# arduboy-gt.net
KiCad netlist of a schematic drawn in EAGLE
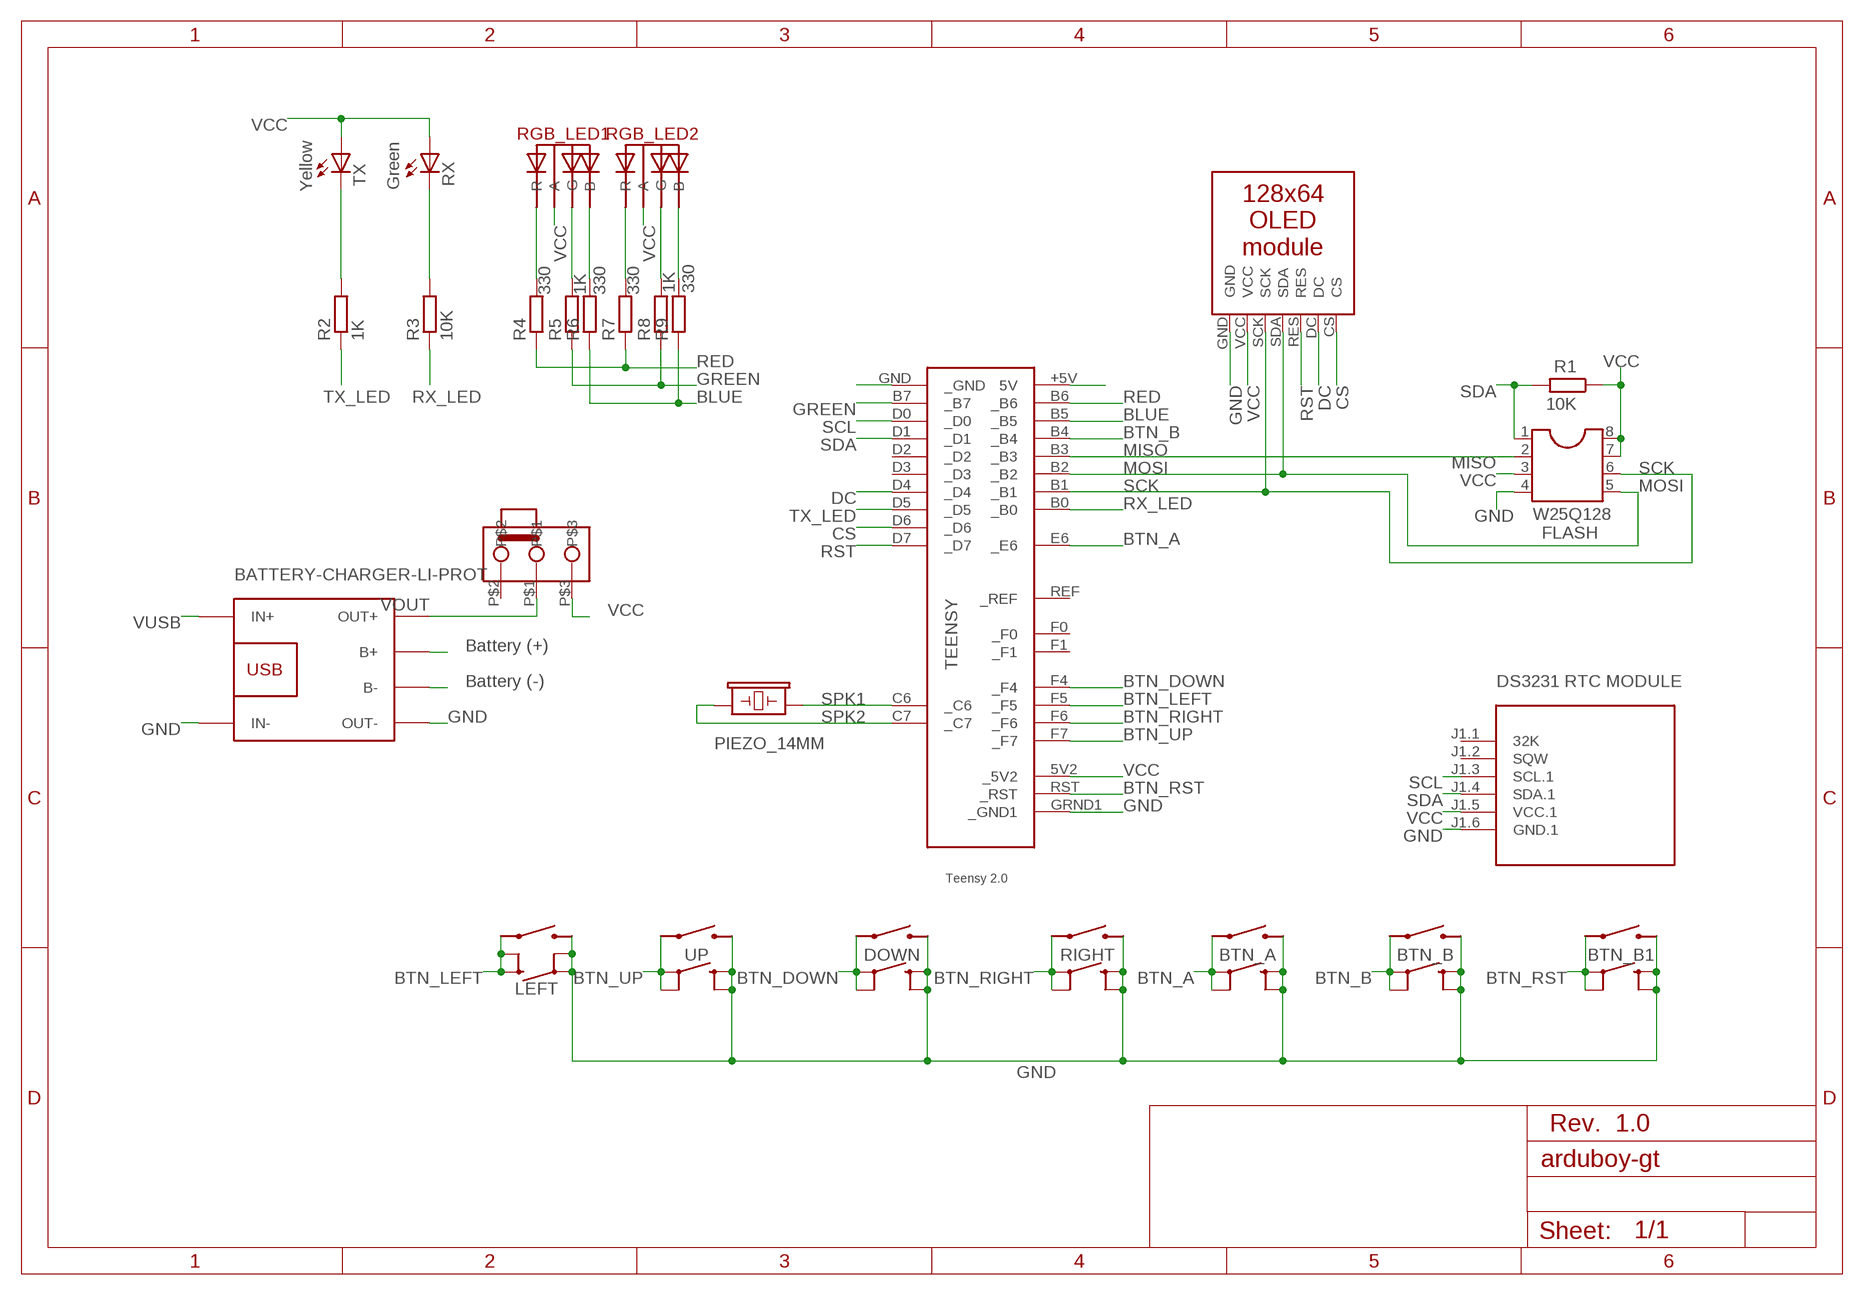
[diagram p0: schematic, sheet 1]

(export (version "E")
  (design (tool "Eeschema 10.0.6"))
  (components
    (comp (ref "BTN_A")
      (value "MOMENTARY-SWITCH-SPST-PTH-6.0MM")
      (footprint "eagle-import:TACTILE_SWITCH_PTH_6.0MM")
      (libsource (lib "eagle-import") (part "MOMENTARY-SWITCH-SPST-PTH-6.0MM"))
    )
    (comp (ref "BTN_A_")
      (value "KAIHLMICROSWITCH")
      (footprint "eagle-import:KAIHLMICROSWITCH")
      (libsource (lib "eagle-import") (part "KAIHLMICROSWITCH"))
    )
    (comp (ref "BTN_B")
      (value "MOMENTARY-SWITCH-SPST-PTH-6.0MM")
      (footprint "eagle-import:TACTILE_SWITCH_PTH_6.0MM")
      (libsource (lib "eagle-import") (part "MOMENTARY-SWITCH-SPST-PTH-6.0MM"))
    )
    (comp (ref "BTN_B1")
      (value "MOMENTARY-SWITCH-SPST-PTH-6.0MM")
      (footprint "eagle-import:TACTILE_SWITCH_PTH_6.0MM")
      (libsource (lib "eagle-import") (part "MOMENTARY-SWITCH-SPST-PTH-6.0MM"))
    )
    (comp (ref "BTN_B_")
      (value "KAIHLMICROSWITCH")
      (footprint "eagle-import:KAIHLMICROSWITCH")
      (libsource (lib "eagle-import") (part "KAIHLMICROSWITCH"))
    )
    (comp (ref "BTN_B_1")
      (value "KAIHLMICROSWITCH")
      (footprint "eagle-import:KAIHLMICROSWITCH")
      (libsource (lib "eagle-import") (part "KAIHLMICROSWITCH"))
    )
    (comp (ref "DOWN")
      (value "MOMENTARY-SWITCH-SPST-PTH-6.0MM")
      (footprint "eagle-import:TACTILE_SWITCH_PTH_6.0MM")
      (libsource (lib "eagle-import") (part "MOMENTARY-SWITCH-SPST-PTH-6.0MM"))
    )
    (comp (ref "DOWN_")
      (value "KAIHLMICROSWITCH")
      (footprint "eagle-import:KAIHLMICROSWITCH")
      (libsource (lib "eagle-import") (part "KAIHLMICROSWITCH"))
    )
    (comp (ref "FLASH")
      (value "W25Q128")
      (footprint "eagle-import:DIL08")
      (libsource (lib "eagle-import") (part "DIL8"))
    )
    (comp (ref "LEFT")
      (value "MOMENTARY-SWITCH-SPST-PTH-6.0MM")
      (footprint "eagle-import:TACTILE_SWITCH_PTH_6.0MM")
      (libsource (lib "eagle-import") (part "MOMENTARY-SWITCH-SPST-PTH-6.0MM"))
    )
    (comp (ref "LEFT_")
      (value "KAIHLMICROSWITCH")
      (footprint "eagle-import:KAIHLMICROSWITCH")
      (libsource (lib "eagle-import") (part "KAIHLMICROSWITCH"))
    )
    (comp (ref "R1")
      (value "10K")
      (footprint "eagle-import:0204_7")
      (libsource (lib "eagle-import") (part "R-EU_0204/7"))
    )
    (comp (ref "R2")
      (value "1K")
      (footprint "eagle-import:0204_7")
      (libsource (lib "eagle-import") (part "R-EU_0204/7"))
    )
    (comp (ref "R3")
      (value "10K")
      (footprint "eagle-import:0204_7")
      (libsource (lib "eagle-import") (part "R-EU_0204/7"))
    )
    (comp (ref "R4")
      (value "330")
      (footprint "eagle-import:0204_7")
      (libsource (lib "eagle-import") (part "R-EU_0204/7"))
    )
    (comp (ref "R5")
      (value "1K")
      (footprint "eagle-import:0204_7")
      (libsource (lib "eagle-import") (part "R-EU_0204/7"))
    )
    (comp (ref "R6")
      (value "330")
      (footprint "eagle-import:0204_7")
      (libsource (lib "eagle-import") (part "R-EU_0204/7"))
    )
    (comp (ref "R7")
      (value "330")
      (footprint "eagle-import:0204_7")
      (libsource (lib "eagle-import") (part "R-EU_0204/7"))
    )
    (comp (ref "R8")
      (value "1K")
      (footprint "eagle-import:0204_7")
      (libsource (lib "eagle-import") (part "R-EU_0204/7"))
    )
    (comp (ref "R9")
      (value "330")
      (footprint "eagle-import:0204_7")
      (libsource (lib "eagle-import") (part "R-EU_0204/7"))
    )
    (comp (ref "RGB_LED1")
      (value "5MMRGBLED-CA")
      (footprint "eagle-import:LED5MMRGB")
      (libsource (lib "eagle-import") (part "5MMRGBLED-CA"))
    )
    (comp (ref "RGB_LED2")
      (value "5MMRGBLED-CA")
      (footprint "eagle-import:LED5MMRGB")
      (libsource (lib "eagle-import") (part "5MMRGBLED-CA"))
    )
    (comp (ref "RIGHT")
      (value "MOMENTARY-SWITCH-SPST-PTH-6.0MM")
      (footprint "eagle-import:TACTILE_SWITCH_PTH_6.0MM")
      (libsource (lib "eagle-import") (part "MOMENTARY-SWITCH-SPST-PTH-6.0MM"))
    )
    (comp (ref "RIGHT_")
      (value "KAIHLMICROSWITCH")
      (footprint "eagle-import:KAIHLMICROSWITCH")
      (libsource (lib "eagle-import") (part "KAIHLMICROSWITCH"))
    )
    (comp (ref "RX")
      (value "TLLG4400")
      (footprint "eagle-import:LED3MM")
      (fields (field (name "MF") "VISHAY SEMICONDUCTOR"))
      (libsource (lib "eagle-import") (part "TLLG4400"))
    )
    (comp (ref "SG1")
      (value "PIEZO_14MM")
      (footprint "eagle-import:PIEZO_14MM")
      (libsource (lib "eagle-import") (part "PIEZO_14MM"))
    )
    (comp (ref "TX")
      (value "TLLY4400")
      (footprint "eagle-import:LED3MM")
      (fields (field (name "MF") "VISHAY SEMICONDUCTOR"))
      (libsource (lib "eagle-import") (part "TLLY4400"))
    )
    (comp (ref "U$1")
      (value "OLED")
      (footprint "eagle-import:OLED")
      (libsource (lib "eagle-import") (part "OLED"))
    )
    (comp (ref "U$2")
      (value "SWITCH")
      (footprint "eagle-import:SWITCH")
      (libsource (lib "eagle-import") (part "SWITCH"))
    )
    (comp (ref "U$3")
      (value "BATTERY-CHARGER-LI-PROT")
      (footprint "eagle-import:BATTERY-CHARGER-LI-PROT")
      (libsource (lib "eagle-import") (part "BATTERY-CHARGER-LI-PROT"))
    )
    (comp (ref "U$6")
      (value "DS3231 RTC MODULE")
      (footprint "eagle-import:RTC-DS3231-AT24C32")
      (libsource (lib "eagle-import") (part "RTC-DS3231-AT24C32"))
    )
    (comp (ref "UP")
      (value "MOMENTARY-SWITCH-SPST-PTH-6.0MM")
      (footprint "eagle-import:TACTILE_SWITCH_PTH_6.0MM")
      (libsource (lib "eagle-import") (part "MOMENTARY-SWITCH-SPST-PTH-6.0MM"))
    )
    (comp (ref "UP_")
      (value "KAIHLMICROSWITCH")
      (footprint "eagle-import:KAIHLMICROSWITCH")
      (libsource (lib "eagle-import") (part "KAIHLMICROSWITCH"))
    )
    (comp (ref "_1")
      (value "TEENSY")
      (footprint "eagle-import:TEENSY")
      (libsource (lib "eagle-import") (part "TEENSY"))
    )
  )
  (nets
    (net (code "1") (name "/BLUE") (class "Default")
      (node (ref "R6") (pin "1") (pinfunction "1_1") (pintype "passive"))
      (node (ref "R9") (pin "1") (pinfunction "1_1") (pintype "passive"))
      (node (ref "_1") (pin "B5") (pinfunction "_B5_B5") (pintype "bidirectional"))
    )
    (net (code "2") (name "/BTN_A") (class "Default")
      (node (ref "BTN_A") (pin "1") (pinfunction "1_1") (pintype "passive"))
      (node (ref "BTN_A") (pin "2") (pinfunction "2_2") (pintype "passive"))
      (node (ref "BTN_A_") (pin "P$1") (pinfunction "P$1_P$1") (pintype "bidirectional"))
      (node (ref "_1") (pin "E6") (pinfunction "_E6_E6") (pintype "bidirectional"))
    )
    (net (code "3") (name "/BTN_B") (class "Default")
      (node (ref "BTN_B") (pin "1") (pinfunction "1_1") (pintype "passive"))
      (node (ref "BTN_B") (pin "2") (pinfunction "2_2") (pintype "passive"))
      (node (ref "BTN_B_") (pin "P$1") (pinfunction "P$1_P$1") (pintype "bidirectional"))
      (node (ref "_1") (pin "B4") (pinfunction "_B4_B4") (pintype "bidirectional"))
    )
    (net (code "4") (name "/BTN_DOWN") (class "Default")
      (node (ref "DOWN") (pin "1") (pinfunction "1_1") (pintype "passive"))
      (node (ref "DOWN") (pin "2") (pinfunction "2_2") (pintype "passive"))
      (node (ref "DOWN_") (pin "P$1") (pinfunction "P$1_P$1") (pintype "bidirectional"))
      (node (ref "_1") (pin "F4") (pinfunction "_F4_F4") (pintype "bidirectional"))
    )
    (net (code "5") (name "/BTN_LEFT") (class "Default")
      (node (ref "LEFT") (pin "3") (pinfunction "3_3") (pintype "passive"))
      (node (ref "LEFT") (pin "4") (pinfunction "4_4") (pintype "passive"))
      (node (ref "LEFT_") (pin "P$1") (pinfunction "P$1_P$1") (pintype "bidirectional"))
      (node (ref "_1") (pin "F5") (pinfunction "_F5_F5") (pintype "bidirectional"))
    )
    (net (code "6") (name "/BTN_RIGHT") (class "Default")
      (node (ref "RIGHT") (pin "1") (pinfunction "1_1") (pintype "passive"))
      (node (ref "RIGHT") (pin "2") (pinfunction "2_2") (pintype "passive"))
      (node (ref "RIGHT_") (pin "P$1") (pinfunction "P$1_P$1") (pintype "bidirectional"))
      (node (ref "_1") (pin "F6") (pinfunction "_F6_F6") (pintype "bidirectional"))
    )
    (net (code "7") (name "/BTN_RST") (class "Default")
      (node (ref "BTN_B1") (pin "1") (pinfunction "1_1") (pintype "passive"))
      (node (ref "BTN_B1") (pin "2") (pinfunction "2_2") (pintype "passive"))
      (node (ref "BTN_B_1") (pin "P$1") (pinfunction "P$1_P$1") (pintype "bidirectional"))
      (node (ref "_1") (pin "RST") (pinfunction "_RST_RST") (pintype "bidirectional"))
    )
    (net (code "8") (name "/BTN_UP") (class "Default")
      (node (ref "UP") (pin "1") (pinfunction "1_1") (pintype "passive"))
      (node (ref "UP") (pin "2") (pinfunction "2_2") (pintype "passive"))
      (node (ref "UP_") (pin "P$1") (pinfunction "P$1_P$1") (pintype "bidirectional"))
      (node (ref "_1") (pin "F7") (pinfunction "_F7_F7") (pintype "bidirectional"))
    )
    (net (code "9") (name "/CS") (class "Default")
      (node (ref "U$1") (pin "CS") (pinfunction "CS_CS") (pintype "input"))
      (node (ref "_1") (pin "D6") (pinfunction "_D6_D6") (pintype "bidirectional"))
    )
    (net (code "10") (name "/DC") (class "Default")
      (node (ref "U$1") (pin "DC") (pinfunction "DC_DC") (pintype "input"))
      (node (ref "_1") (pin "D4") (pinfunction "_D4_D4") (pintype "bidirectional"))
    )
    (net (code "11") (name "/GND") (class "Default")
      (node (ref "BTN_A") (pin "3") (pinfunction "3_3") (pintype "passive"))
      (node (ref "BTN_A") (pin "4") (pinfunction "4_4") (pintype "passive"))
      (node (ref "BTN_A_") (pin "P$2") (pinfunction "P$2_P$2") (pintype "bidirectional"))
      (node (ref "BTN_B") (pin "3") (pinfunction "3_3") (pintype "passive"))
      (node (ref "BTN_B") (pin "4") (pinfunction "4_4") (pintype "passive"))
      (node (ref "BTN_B1") (pin "3") (pinfunction "3_3") (pintype "passive"))
      (node (ref "BTN_B1") (pin "4") (pinfunction "4_4") (pintype "passive"))
      (node (ref "BTN_B_") (pin "P$2") (pinfunction "P$2_P$2") (pintype "bidirectional"))
      (node (ref "BTN_B_1") (pin "P$2") (pinfunction "P$2_P$2") (pintype "bidirectional"))
      (node (ref "DOWN") (pin "3") (pinfunction "3_3") (pintype "passive"))
      (node (ref "DOWN") (pin "4") (pinfunction "4_4") (pintype "passive"))
      (node (ref "DOWN_") (pin "P$2") (pinfunction "P$2_P$2") (pintype "bidirectional"))
      (node (ref "FLASH") (pin "4") (pinfunction "4_4") (pintype "passive"))
      (node (ref "LEFT") (pin "1") (pinfunction "1_1") (pintype "passive"))
      (node (ref "LEFT") (pin "2") (pinfunction "2_2") (pintype "passive"))
      (node (ref "LEFT_") (pin "P$2") (pinfunction "P$2_P$2") (pintype "bidirectional"))
      (node (ref "RIGHT") (pin "3") (pinfunction "3_3") (pintype "passive"))
      (node (ref "RIGHT") (pin "4") (pinfunction "4_4") (pintype "passive"))
      (node (ref "RIGHT_") (pin "P$2") (pinfunction "P$2_P$2") (pintype "bidirectional"))
      (node (ref "U$1") (pin "GND") (pinfunction "GND_GND") (pintype "power_in"))
      (node (ref "U$3") (pin "IN-") (pinfunction "IN-_IN-") (pintype "bidirectional"))
      (node (ref "U$3") (pin "OUT-") (pinfunction "OUT-_OUT-") (pintype "bidirectional"))
      (node (ref "U$6") (pin "J1.6") (pinfunction "GND.1_J1.6") (pintype "power_in"))
      (node (ref "UP") (pin "3") (pinfunction "3_3") (pintype "passive"))
      (node (ref "UP") (pin "4") (pinfunction "4_4") (pintype "passive"))
      (node (ref "UP_") (pin "P$2") (pinfunction "P$2_P$2") (pintype "bidirectional"))
      (node (ref "_1") (pin "GND") (pinfunction "_GND_GND") (pintype "bidirectional"))
      (node (ref "_1") (pin "GRND1") (pinfunction "_GND1_GRND1") (pintype "bidirectional"))
    )
    (net (code "12") (name "/GREEN") (class "Default")
      (node (ref "R5") (pin "1") (pinfunction "1_1") (pintype "passive"))
      (node (ref "R8") (pin "1") (pinfunction "1_1") (pintype "passive"))
      (node (ref "_1") (pin "B7") (pinfunction "_B7_B7") (pintype "bidirectional"))
    )
    (net (code "13") (name "/MISO") (class "Default")
      (node (ref "FLASH") (pin "2") (pinfunction "2_2") (pintype "passive"))
      (node (ref "_1") (pin "B3") (pinfunction "_B3_B3") (pintype "bidirectional"))
    )
    (net (code "14") (name "/MOSI") (class "Default")
      (node (ref "FLASH") (pin "5") (pinfunction "5_5") (pintype "passive"))
      (node (ref "U$1") (pin "SDA") (pinfunction "SDA_SDA") (pintype "input"))
      (node (ref "_1") (pin "B2") (pinfunction "_B2_B2") (pintype "bidirectional"))
    )
    (net (code "15") (name "/RED") (class "Default")
      (node (ref "R4") (pin "1") (pinfunction "1_1") (pintype "passive"))
      (node (ref "R7") (pin "1") (pinfunction "1_1") (pintype "passive"))
      (node (ref "_1") (pin "B6") (pinfunction "_B6_B6") (pintype "bidirectional"))
    )
    (net (code "16") (name "/RST") (class "Default")
      (node (ref "U$1") (pin "RES") (pinfunction "RES_RES") (pintype "input"))
      (node (ref "_1") (pin "D7") (pinfunction "_D7_D7") (pintype "bidirectional"))
    )
    (net (code "17") (name "/RX_LED") (class "Default")
      (node (ref "R3") (pin "1") (pinfunction "1_1") (pintype "passive"))
      (node (ref "_1") (pin "B0") (pinfunction "_B0_B0") (pintype "bidirectional"))
    )
    (net (code "18") (name "/SCK") (class "Default")
      (node (ref "FLASH") (pin "6") (pinfunction "6_6") (pintype "passive"))
      (node (ref "U$1") (pin "SCK") (pinfunction "SCK_SCK") (pintype "input"))
      (node (ref "_1") (pin "B1") (pinfunction "_B1_B1") (pintype "bidirectional"))
    )
    (net (code "19") (name "/SCL") (class "Default")
      (node (ref "U$6") (pin "J1.3") (pinfunction "SCL.1_J1.3") (pintype "bidirectional"))
      (node (ref "_1") (pin "D0") (pinfunction "_D0_D0") (pintype "bidirectional"))
    )
    (net (code "20") (name "/SDA") (class "Default")
      (node (ref "FLASH") (pin "1") (pinfunction "1_1") (pintype "passive"))
      (node (ref "R1") (pin "2") (pinfunction "2_2") (pintype "passive"))
      (node (ref "U$6") (pin "J1.4") (pinfunction "SDA.1_J1.4") (pintype "bidirectional"))
      (node (ref "_1") (pin "D1") (pinfunction "_D1_D1") (pintype "bidirectional"))
    )
    (net (code "21") (name "/SPK1") (class "Default")
      (node (ref "SG1") (pin "P$2") (pinfunction "P$2_P$2") (pintype "passive"))
      (node (ref "_1") (pin "C6") (pinfunction "_C6_C6") (pintype "bidirectional"))
    )
    (net (code "22") (name "/SPK2") (class "Default")
      (node (ref "SG1") (pin "P$1") (pinfunction "P$1_P$1") (pintype "passive"))
      (node (ref "_1") (pin "C7") (pinfunction "_C7_C7") (pintype "bidirectional"))
    )
    (net (code "23") (name "/TX_LED") (class "Default")
      (node (ref "R2") (pin "1") (pinfunction "1_1") (pintype "passive"))
      (node (ref "_1") (pin "D5") (pinfunction "_D5_D5") (pintype "bidirectional"))
    )
    (net (code "24") (name "/VCC") (class "Default")
      (node (ref "FLASH") (pin "3") (pinfunction "3_3") (pintype "passive"))
      (node (ref "FLASH") (pin "7") (pinfunction "7_7") (pintype "passive"))
      (node (ref "FLASH") (pin "8") (pinfunction "8_8") (pintype "passive"))
      (node (ref "R1") (pin "1") (pinfunction "1_1") (pintype "passive"))
      (node (ref "RGB_LED1") (pin "C$1") (pinfunction "A_C$1") (pintype "bidirectional"))
      (node (ref "RGB_LED2") (pin "C$1") (pinfunction "A_C$1") (pintype "bidirectional"))
      (node (ref "RX") (pin "A") (pinfunction "A_A") (pintype "passive"))
      (node (ref "TX") (pin "A") (pinfunction "A_A") (pintype "passive"))
      (node (ref "U$1") (pin "VCC") (pinfunction "VCC_VCC") (pintype "power_in"))
      (node (ref "U$2") (pin "P$3") (pinfunction "P$3_P$3") (pintype "bidirectional"))
      (node (ref "U$6") (pin "J1.5") (pinfunction "VCC.1_J1.5") (pintype "power_in"))
      (node (ref "_1") (pin "+5V") (pinfunction "5V_+5V") (pintype "bidirectional"))
      (node (ref "_1") (pin "5V2") (pinfunction "_5V2_5V2") (pintype "bidirectional"))
    )
    (net (code "25") (name "/VOUT") (class "Default")
      (node (ref "U$2") (pin "P$1") (pinfunction "P$1_P$1") (pintype "bidirectional"))
      (node (ref "U$3") (pin "OUT+") (pinfunction "OUT+_OUT+") (pintype "bidirectional"))
    )
    (net (code "26") (name "/VUSB") (class "Default")
      (node (ref "U$3") (pin "IN+") (pinfunction "IN+_IN+") (pintype "bidirectional"))
    )
    (net (code "27") (name "Net-(RGB_LED1-B)") (class "Default")
      (node (ref "R6") (pin "2") (pinfunction "2_2") (pintype "passive"))
      (node (ref "RGB_LED1") (pin "B$1") (pinfunction "B_B$1") (pintype "bidirectional"))
    )
    (net (code "28") (name "Net-(RGB_LED1-G)") (class "Default")
      (node (ref "R5") (pin "2") (pinfunction "2_2") (pintype "passive"))
      (node (ref "RGB_LED1") (pin "G$1") (pinfunction "G_G$1") (pintype "bidirectional"))
    )
    (net (code "29") (name "Net-(RGB_LED1-R)") (class "Default")
      (node (ref "R4") (pin "2") (pinfunction "2_2") (pintype "passive"))
      (node (ref "RGB_LED1") (pin "R$1") (pinfunction "R_R$1") (pintype "bidirectional"))
    )
    (net (code "30") (name "Net-(RGB_LED2-B)") (class "Default")
      (node (ref "R9") (pin "2") (pinfunction "2_2") (pintype "passive"))
      (node (ref "RGB_LED2") (pin "B$1") (pinfunction "B_B$1") (pintype "bidirectional"))
    )
    (net (code "31") (name "Net-(RGB_LED2-G)") (class "Default")
      (node (ref "R8") (pin "2") (pinfunction "2_2") (pintype "passive"))
      (node (ref "RGB_LED2") (pin "G$1") (pinfunction "G_G$1") (pintype "bidirectional"))
    )
    (net (code "32") (name "Net-(RGB_LED2-R)") (class "Default")
      (node (ref "R7") (pin "2") (pinfunction "2_2") (pintype "passive"))
      (node (ref "RGB_LED2") (pin "R$1") (pinfunction "R_R$1") (pintype "bidirectional"))
    )
    (net (code "33") (name "Net-(RX-C)") (class "Default")
      (node (ref "R3") (pin "2") (pinfunction "2_2") (pintype "passive"))
      (node (ref "RX") (pin "K") (pinfunction "C_K") (pintype "passive"))
    )
    (net (code "34") (name "Net-(TX-C)") (class "Default")
      (node (ref "R2") (pin "2") (pinfunction "2_2") (pintype "passive"))
      (node (ref "TX") (pin "K") (pinfunction "C_K") (pintype "passive"))
    )
    (net (code "35") (name "unconnected-(U$2-PadP$2)") (class "Default")
      (node (ref "U$2") (pin "P$2") (pinfunction "P$2_P$2") (pintype "bidirectional"))
    )
    (net (code "36") (name "unconnected-(U$3-PadB+)") (class "Default")
      (node (ref "U$3") (pin "B+") (pinfunction "B+_B+") (pintype "bidirectional"))
    )
    (net (code "37") (name "unconnected-(U$3-PadB-)") (class "Default")
      (node (ref "U$3") (pin "B-") (pinfunction "B-_B-") (pintype "bidirectional"))
    )
    (net (code "38") (name "unconnected-(U$6-32K-PadJ1.1)") (class "Default")
      (node (ref "U$6") (pin "J1.1") (pinfunction "32K_J1.1") (pintype "bidirectional"))
    )
    (net (code "39") (name "unconnected-(U$6-SQW-PadJ1.2)") (class "Default")
      (node (ref "U$6") (pin "J1.2") (pinfunction "SQW_J1.2") (pintype "bidirectional"))
    )
    (net (code "40") (name "unconnected-(_1-_D2-PadD2)") (class "Default")
      (node (ref "_1") (pin "D2") (pinfunction "_D2_D2") (pintype "bidirectional"))
    )
    (net (code "41") (name "unconnected-(_1-_D3-PadD3)") (class "Default")
      (node (ref "_1") (pin "D3") (pinfunction "_D3_D3") (pintype "bidirectional"))
    )
    (net (code "42") (name "unconnected-(_1-_F0-PadF0)") (class "Default")
      (node (ref "_1") (pin "F0") (pinfunction "_F0_F0") (pintype "bidirectional"))
    )
    (net (code "43") (name "unconnected-(_1-_F1-PadF1)") (class "Default")
      (node (ref "_1") (pin "F1") (pinfunction "_F1_F1") (pintype "bidirectional"))
    )
    (net (code "44") (name "unconnected-(_1-_REF-PadREF)") (class "Default")
      (node (ref "_1") (pin "REF") (pinfunction "_REF_REF") (pintype "bidirectional"))
    )
  )
)
